# pi-frontpanel.net
KiCad netlist of a schematic drawn in EAGLE
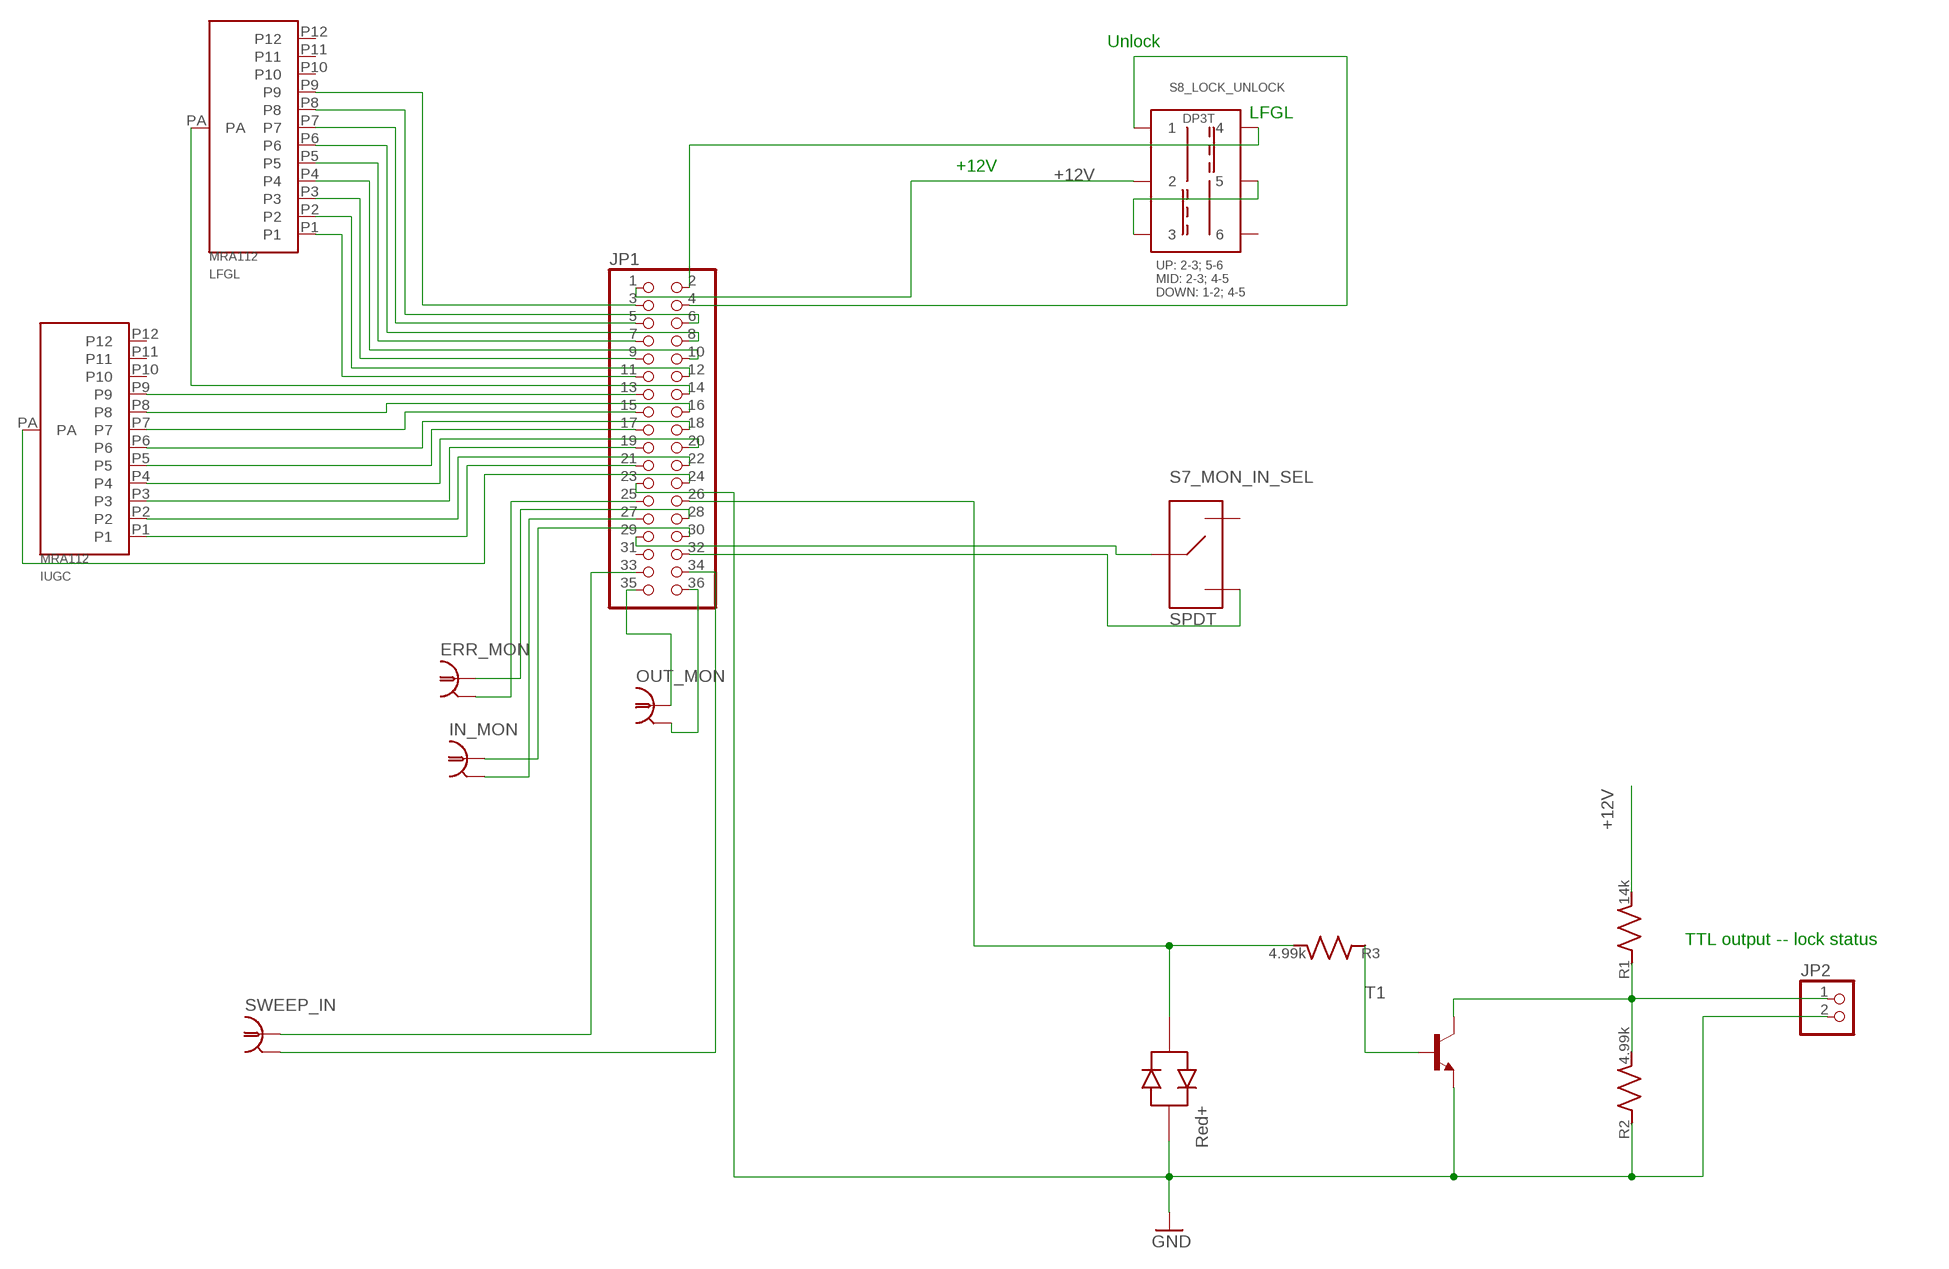
[diagram p0: schematic, sheet 1]

(export (version "E")
  (design (tool "Eeschema 10.0.6"))
  (components
    (comp (ref "ERR_MON")
      (value "BNC-V")
      (footprint "eagle-import:BNC-V")
      (fields (field (name "PARTNO") "A32262-ND"))
      (libsource (lib "eagle-import") (part "BNC-V"))
    )
    (comp (ref "IN_MON")
      (value "BNC-V")
      (footprint "eagle-import:BNC-V")
      (fields (field (name "PARTNO") "A32262-ND"))
      (libsource (lib "eagle-import") (part "BNC-V"))
    )
    (comp (ref "IUGC")
      (value "MRA112")
      (footprint "eagle-import:MRA112")
      (fields (field (name "PARTNO") "360-2368-ND"))
      (libsource (lib "eagle-import") (part "MRA112"))
    )
    (comp (ref "JP1")
      (value "PINHD-2X18")
      (footprint "eagle-import:2X18")
      (fields (field (name "PARTNO") "S7086-ND"))
      (libsource (lib "eagle-import") (part "PINHD-2X18"))
    )
    (comp (ref "JP2")
      (value "PINHD-1X2")
      (footprint "eagle-import:1X02")
      (fields (field (name "PARTNO") "A1921-ND"))
      (libsource (lib "eagle-import") (part "PINHD-1X2"))
    )
    (comp (ref "LED")
      (value "SSL-LX5093IGW")
      (footprint "eagle-import:LED-TH")
      (fields (field (name "PARTNO") "67-2207-ND"))
      (libsource (lib "eagle-import") (part "SSL-LX5093IGW"))
    )
    (comp (ref "LFGL")
      (value "MRA112")
      (footprint "eagle-import:MRA112")
      (fields (field (name "PARTNO") "360-2368-ND"))
      (libsource (lib "eagle-import") (part "MRA112"))
    )
    (comp (ref "OUT_MON")
      (value "BNC-V")
      (footprint "eagle-import:BNC-V")
      (fields (field (name "PARTNO") "A32262-ND"))
      (libsource (lib "eagle-import") (part "BNC-V"))
    )
    (comp (ref "R1")
      (value "14k")
      (footprint "eagle-import:R_1206")
      (fields (field (name "PARTNO") "P14.0KFCT-ND"))
      (libsource (lib "eagle-import") (part "R_SMDR1206"))
    )
    (comp (ref "R2")
      (value "4.99k")
      (footprint "eagle-import:R_1206")
      (fields (field (name "PARTNO") "P4.99KFCT-ND"))
      (libsource (lib "eagle-import") (part "R_SMDR1206"))
    )
    (comp (ref "R3")
      (value "4.99k")
      (footprint "eagle-import:R_1206")
      (fields (field (name "PARTNO") "P4.99KFCT-ND"))
      (libsource (lib "eagle-import") (part "R_SMDR1206"))
    )
    (comp (ref "S7_MON_IN_SEL")
      (value "SPDT")
      (footprint "eagle-import:SPDT_LUG")
      (fields (field (name "PARTNO") "450-1523-ND"))
      (libsource (lib "eagle-import") (part "SPDT"))
    )
    (comp (ref "S8_LOCK_UNLOCK")
      (value "DP3T")
      (footprint "eagle-import:SP3T_LUG")
      (fields (field (name "PARTNUM") "450-1536-ND"))
      (libsource (lib "eagle-import") (part "DP3T"))
    )
    (comp (ref "SWEEP_IN")
      (value "BNC-V")
      (footprint "eagle-import:BNC-V")
      (fields (field (name "PARTNO") "A32262-ND"))
      (libsource (lib "eagle-import") (part "BNC-V"))
    )
    (comp (ref "T1")
      (value "MMBT2222ALT1-NPN-SOT23-BEC")
      (footprint "eagle-import:SOT23-BEC")
      (fields (field (name "PARTNO") "MMBT2222A-FDICT-ND"))
      (libsource (lib "eagle-import") (part "-NPN-SOT23-BECMMBT2222ALT1"))
    )
  )
  (nets
    (net (code "1") (name "/+12V") (class "Default")
      (node (ref "JP1") (pin "1") (pinfunction "1_1") (pintype "passive"))
      (node (ref "R1") (pin "P$2") (pinfunction "2_P$2") (pintype "passive"))
      (node (ref "S8_LOCK_UNLOCK") (pin "2") (pinfunction "2_2") (pintype "bidirectional"))
    )
    (net (code "2") (name "GND") (class "Default")
      (node (ref "JP1") (pin "23") (pinfunction "23_23") (pintype "passive"))
      (node (ref "JP2") (pin "2") (pinfunction "2_2") (pintype "passive"))
      (node (ref "LED") (pin "P$2") (pinfunction "RED+_P$2") (pintype "bidirectional"))
      (node (ref "R2") (pin "P$1") (pinfunction "1_P$1") (pintype "passive"))
      (node (ref "T1") (pin "E") (pinfunction "E_E") (pintype "passive"))
    )
    (net (code "3") (name "Net-(ERR_MON-Pad1)") (class "Default")
      (node (ref "ERR_MON") (pin "1") (pinfunction "1_1") (pintype "passive"))
      (node (ref "JP1") (pin "28") (pinfunction "28_28") (pintype "passive"))
    )
    (net (code "4") (name "Net-(ERR_MON-Pad2)") (class "Default")
      (node (ref "ERR_MON") (pin "2") (pinfunction "2_2") (pintype "passive"))
      (node (ref "JP1") (pin "25") (pinfunction "25_25") (pintype "passive"))
    )
    (net (code "5") (name "Net-(IN_MON-Pad1)") (class "Default")
      (node (ref "IN_MON") (pin "1") (pinfunction "1_1") (pintype "passive"))
      (node (ref "JP1") (pin "30") (pinfunction "30_30") (pintype "passive"))
    )
    (net (code "6") (name "Net-(IN_MON-Pad2)") (class "Default")
      (node (ref "IN_MON") (pin "2") (pinfunction "2_2") (pintype "passive"))
      (node (ref "JP1") (pin "27") (pinfunction "27_27") (pintype "passive"))
    )
    (net (code "7") (name "Net-(IUGC-PadP1)") (class "Default")
      (node (ref "IUGC") (pin "P1") (pinfunction "P1_P1") (pintype "bidirectional"))
      (node (ref "JP1") (pin "21") (pinfunction "21_21") (pintype "passive"))
    )
    (net (code "8") (name "Net-(IUGC-PadP2)") (class "Default")
      (node (ref "IUGC") (pin "P2") (pinfunction "P2_P2") (pintype "bidirectional"))
      (node (ref "JP1") (pin "22") (pinfunction "22_22") (pintype "passive"))
    )
    (net (code "9") (name "Net-(IUGC-PadP3)") (class "Default")
      (node (ref "IUGC") (pin "P3") (pinfunction "P3_P3") (pintype "bidirectional"))
      (node (ref "JP1") (pin "19") (pinfunction "19_19") (pintype "passive"))
    )
    (net (code "10") (name "Net-(IUGC-PadP4)") (class "Default")
      (node (ref "IUGC") (pin "P4") (pinfunction "P4_P4") (pintype "bidirectional"))
      (node (ref "JP1") (pin "20") (pinfunction "20_20") (pintype "passive"))
    )
    (net (code "11") (name "Net-(IUGC-PadP5)") (class "Default")
      (node (ref "IUGC") (pin "P5") (pinfunction "P5_P5") (pintype "bidirectional"))
      (node (ref "JP1") (pin "17") (pinfunction "17_17") (pintype "passive"))
    )
    (net (code "12") (name "Net-(IUGC-PadP6)") (class "Default")
      (node (ref "IUGC") (pin "P6") (pinfunction "P6_P6") (pintype "bidirectional"))
      (node (ref "JP1") (pin "18") (pinfunction "18_18") (pintype "passive"))
    )
    (net (code "13") (name "Net-(IUGC-PadP7)") (class "Default")
      (node (ref "IUGC") (pin "P7") (pinfunction "P7_P7") (pintype "bidirectional"))
      (node (ref "JP1") (pin "15") (pinfunction "15_15") (pintype "passive"))
    )
    (net (code "14") (name "Net-(IUGC-PadP8)") (class "Default")
      (node (ref "IUGC") (pin "P8") (pinfunction "P8_P8") (pintype "bidirectional"))
      (node (ref "JP1") (pin "16") (pinfunction "16_16") (pintype "passive"))
    )
    (net (code "15") (name "Net-(IUGC-PadP9)") (class "Default")
      (node (ref "IUGC") (pin "P9") (pinfunction "P9_P9") (pintype "bidirectional"))
      (node (ref "JP1") (pin "13") (pinfunction "13_13") (pintype "passive"))
    )
    (net (code "16") (name "Net-(IUGC-PadPA)") (class "Default")
      (node (ref "IUGC") (pin "PA") (pinfunction "PA_PA") (pintype "bidirectional"))
      (node (ref "JP1") (pin "24") (pinfunction "24_24") (pintype "passive"))
    )
    (net (code "17") (name "Net-(JP1-Pad2)") (class "Default")
      (node (ref "JP1") (pin "2") (pinfunction "2_2") (pintype "passive"))
      (node (ref "S8_LOCK_UNLOCK") (pin "4") (pinfunction "4_4") (pintype "bidirectional"))
    )
    (net (code "18") (name "Net-(JP1-Pad3)") (class "Default")
      (node (ref "JP1") (pin "3") (pinfunction "3_3") (pintype "passive"))
      (node (ref "LFGL") (pin "P9") (pinfunction "P9_P9") (pintype "bidirectional"))
    )
    (net (code "19") (name "Net-(JP1-Pad4)") (class "Default")
      (node (ref "JP1") (pin "4") (pinfunction "4_4") (pintype "passive"))
      (node (ref "S8_LOCK_UNLOCK") (pin "1") (pinfunction "1_1") (pintype "bidirectional"))
    )
    (net (code "20") (name "Net-(JP1-Pad5)") (class "Default")
      (node (ref "JP1") (pin "5") (pinfunction "5_5") (pintype "passive"))
      (node (ref "LFGL") (pin "P7") (pinfunction "P7_P7") (pintype "bidirectional"))
    )
    (net (code "21") (name "Net-(JP1-Pad6)") (class "Default")
      (node (ref "JP1") (pin "6") (pinfunction "6_6") (pintype "passive"))
      (node (ref "LFGL") (pin "P8") (pinfunction "P8_P8") (pintype "bidirectional"))
    )
    (net (code "22") (name "Net-(JP1-Pad7)") (class "Default")
      (node (ref "JP1") (pin "7") (pinfunction "7_7") (pintype "passive"))
      (node (ref "LFGL") (pin "P5") (pinfunction "P5_P5") (pintype "bidirectional"))
    )
    (net (code "23") (name "Net-(JP1-Pad8)") (class "Default")
      (node (ref "JP1") (pin "8") (pinfunction "8_8") (pintype "passive"))
      (node (ref "LFGL") (pin "P6") (pinfunction "P6_P6") (pintype "bidirectional"))
    )
    (net (code "24") (name "Net-(JP1-Pad9)") (class "Default")
      (node (ref "JP1") (pin "9") (pinfunction "9_9") (pintype "passive"))
      (node (ref "LFGL") (pin "P3") (pinfunction "P3_P3") (pintype "bidirectional"))
    )
    (net (code "25") (name "Net-(JP1-Pad10)") (class "Default")
      (node (ref "JP1") (pin "10") (pinfunction "10_10") (pintype "passive"))
      (node (ref "LFGL") (pin "P4") (pinfunction "P4_P4") (pintype "bidirectional"))
    )
    (net (code "26") (name "Net-(JP1-Pad11)") (class "Default")
      (node (ref "JP1") (pin "11") (pinfunction "11_11") (pintype "passive"))
      (node (ref "LFGL") (pin "P1") (pinfunction "P1_P1") (pintype "bidirectional"))
    )
    (net (code "27") (name "Net-(JP1-Pad12)") (class "Default")
      (node (ref "JP1") (pin "12") (pinfunction "12_12") (pintype "passive"))
      (node (ref "LFGL") (pin "P2") (pinfunction "P2_P2") (pintype "bidirectional"))
    )
    (net (code "28") (name "Net-(JP1-Pad14)") (class "Default")
      (node (ref "JP1") (pin "14") (pinfunction "14_14") (pintype "passive"))
      (node (ref "LFGL") (pin "PA") (pinfunction "PA_PA") (pintype "bidirectional"))
    )
    (net (code "29") (name "Net-(JP1-Pad33)") (class "Default")
      (node (ref "JP1") (pin "33") (pinfunction "33_33") (pintype "passive"))
      (node (ref "SWEEP_IN") (pin "1") (pinfunction "1_1") (pintype "passive"))
    )
    (net (code "30") (name "Net-(JP1-Pad34)") (class "Default")
      (node (ref "JP1") (pin "34") (pinfunction "34_34") (pintype "passive"))
      (node (ref "SWEEP_IN") (pin "2") (pinfunction "2_2") (pintype "passive"))
    )
    (net (code "31") (name "Net-(JP1-Pad35)") (class "Default")
      (node (ref "JP1") (pin "35") (pinfunction "35_35") (pintype "passive"))
      (node (ref "OUT_MON") (pin "1") (pinfunction "1_1") (pintype "passive"))
    )
    (net (code "32") (name "Net-(JP1-Pad36)") (class "Default")
      (node (ref "JP1") (pin "36") (pinfunction "36_36") (pintype "passive"))
      (node (ref "OUT_MON") (pin "2") (pinfunction "2_2") (pintype "passive"))
    )
    (net (code "33") (name "Net-(LED-GREEN+)") (class "Default")
      (node (ref "JP1") (pin "26") (pinfunction "26_26") (pintype "passive"))
      (node (ref "LED") (pin "P$1") (pinfunction "GREEN+_P$1") (pintype "bidirectional"))
      (node (ref "R3") (pin "P$2") (pinfunction "2_P$2") (pintype "passive"))
    )
    (net (code "34") (name "Net-(R1-1)") (class "Default")
      (node (ref "JP2") (pin "1") (pinfunction "1_1") (pintype "passive"))
      (node (ref "R1") (pin "P$1") (pinfunction "1_P$1") (pintype "passive"))
      (node (ref "R2") (pin "P$2") (pinfunction "2_P$2") (pintype "passive"))
      (node (ref "T1") (pin "C") (pinfunction "C_C") (pintype "passive"))
    )
    (net (code "35") (name "Net-(R3-1)") (class "Default")
      (node (ref "R3") (pin "P$1") (pinfunction "1_P$1") (pintype "passive"))
      (node (ref "T1") (pin "B") (pinfunction "B_B") (pintype "passive"))
    )
    (net (code "36") (name "Net-(S7_MON_IN_SEL-P$2)") (class "Default")
      (node (ref "JP1") (pin "29") (pinfunction "29_29") (pintype "passive"))
      (node (ref "S7_MON_IN_SEL") (pin "2") (pinfunction "P$2_2") (pintype "bidirectional"))
    )
    (net (code "37") (name "Net-(S7_MON_IN_SEL-P$3)") (class "Default")
      (node (ref "JP1") (pin "32") (pinfunction "32_32") (pintype "passive"))
      (node (ref "S7_MON_IN_SEL") (pin "3") (pinfunction "P$3_3") (pintype "bidirectional"))
    )
    (net (code "38") (name "Net-(S8_LOCK_UNLOCK-Pad3)") (class "Default")
      (node (ref "S8_LOCK_UNLOCK") (pin "3") (pinfunction "3_3") (pintype "bidirectional"))
      (node (ref "S8_LOCK_UNLOCK") (pin "5") (pinfunction "5_5") (pintype "bidirectional"))
    )
    (net (code "39") (name "unconnected-(IUGC-PadP10)") (class "Default")
      (node (ref "IUGC") (pin "P10") (pinfunction "P10_P10") (pintype "bidirectional"))
    )
    (net (code "40") (name "unconnected-(IUGC-PadP11)") (class "Default")
      (node (ref "IUGC") (pin "P11") (pinfunction "P11_P11") (pintype "bidirectional"))
    )
    (net (code "41") (name "unconnected-(IUGC-PadP12)") (class "Default")
      (node (ref "IUGC") (pin "P12") (pinfunction "P12_P12") (pintype "bidirectional"))
    )
    (net (code "42") (name "unconnected-(JP1-Pad31)") (class "Default")
      (node (ref "JP1") (pin "31") (pinfunction "31_31") (pintype "passive"))
    )
    (net (code "43") (name "unconnected-(LFGL-PadP10)") (class "Default")
      (node (ref "LFGL") (pin "P10") (pinfunction "P10_P10") (pintype "bidirectional"))
    )
    (net (code "44") (name "unconnected-(LFGL-PadP11)") (class "Default")
      (node (ref "LFGL") (pin "P11") (pinfunction "P11_P11") (pintype "bidirectional"))
    )
    (net (code "45") (name "unconnected-(LFGL-PadP12)") (class "Default")
      (node (ref "LFGL") (pin "P12") (pinfunction "P12_P12") (pintype "bidirectional"))
    )
    (net (code "46") (name "unconnected-(S7_MON_IN_SEL-P$1-Pad1)") (class "Default")
      (node (ref "S7_MON_IN_SEL") (pin "1") (pinfunction "P$1_1") (pintype "bidirectional"))
    )
    (net (code "47") (name "unconnected-(S8_LOCK_UNLOCK-Pad6)") (class "Default")
      (node (ref "S8_LOCK_UNLOCK") (pin "6") (pinfunction "6_6") (pintype "bidirectional"))
    )
  )
)
